# GZ7_1_x-SIM800C.net
KiCad netlist of a schematic drawn in Altium Designer
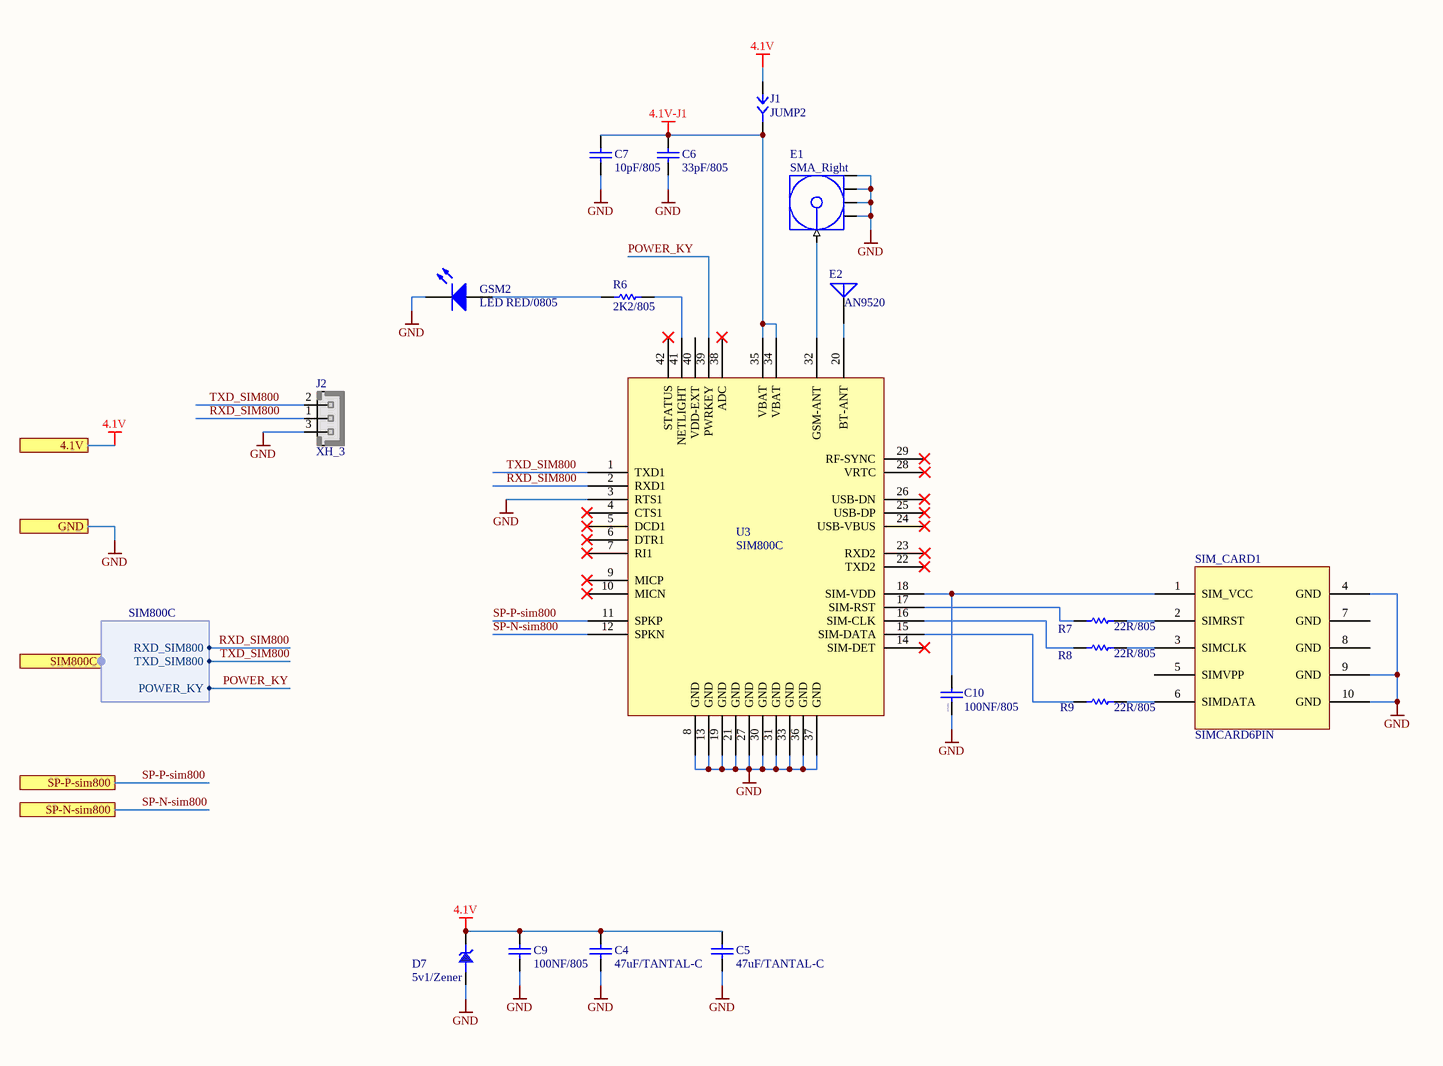
[diagram p0: GZ7_1_x-SIM800C.SchDoc]

(export (version "E")
  (design (tool "Eeschema 10.0.6"))
  (components
    (comp (ref "C4")
      (value "47uF/TANTAL-C")
      (footprint "C-TT1")
      (description "TANTAL")
      (libsource (lib "Miscellaneous Devices") (part "Cap Semi"))
    )
    (comp (ref "C5")
      (value "47uF/TANTAL-C")
      (footprint "C-TT1")
      (description "TANTAL")
      (libsource (lib "Miscellaneous Devices") (part "Cap Semi"))
    )
    (comp (ref "C6")
      (value "33pF/805")
      (footprint "MY805 COP")
      (description "CAP 0805")
      (fields (field (name "PUBLISHER") "Altium Limited"))
      (libsource (lib "Miscellaneous Devices") (part "Cap Semi"))
    )
    (comp (ref "C7")
      (value "10pF/805")
      (footprint "MY805 COP")
      (description "CAP 0805")
      (fields (field (name "PUBLISHER") "Altium Limited"))
      (libsource (lib "Miscellaneous Devices") (part "Cap Semi"))
    )
    (comp (ref "C9")
      (value "100NF/805")
      (footprint "MY805 COP")
      (description "CAP 0805")
      (fields (field (name "PUBLISHER") "Altium Limited"))
      (libsource (lib "Miscellaneous Devices") (part "Cap Semi"))
    )
    (comp (ref "C10")
      (value "100NF/805")
      (footprint "MY805 COP")
      (description "CAP 0805")
      (libsource (lib "GZ8_4_0") (part "CAP"))
    )
    (comp (ref "D7")
      (value "5v1/Zener")
      (footprint "my-DO5X.1.5")
      (libsource (lib "My Diods") (part "Zener"))
    )
    (comp (ref "E1")
      (value "SMA_Right")
      (footprint "MCX5.08-H5")
      (description "50 Ohm Impedance")
      (fields (field (name "PUBLISHER") "Altium Limited"))
      (libsource (lib "Miscellaneous Connectors") (part "COAX-F"))
    )
    (comp (ref "E2")
      (value "AN9520")
      (footprint "ANT-SMD")
      (description "Multilayer Chip Antenna")
      (fields (field (name "PUBLISHER") "Altium Limited"))
      (libsource (lib "Miscellaneous Devices") (part "Antenna"))
    )
    (comp (ref "GSM2")
      (value "LED RED/0805")
      (footprint "LED_SMD_0805")
      (fields (field (name "PUBLISHER") "Altium Limited"))
      (libsource (lib "Miscellaneous Devices") (part "LED2"))
    )
    (comp (ref "J1") (value "JUMP2") (footprint "JUMP3") (libsource (lib "Ebrahim") (part "JUMP2")))
    (comp (ref "J2")
      (value "XH_3")
      (footprint "XH_3")
      (description "PW10-x-M, JST-BxB-XH-A pitch: 2.5mm, 3A/250v")
      (fields (field (name "MANF") "JST") (field (name "MANF_P#") "B3B-XH-A"))
      (libsource (lib "altium-import") (part "root_0_XH_3_"))
    )
    (comp (ref "R6")
      (value "2K2/805")
      (footprint "my805")
      (description "RES 805")
      (libsource (lib "Miscellaneous Devices") (part "Res1"))
    )
    (comp (ref "R7")
      (value "22R/805")
      (footprint "my805")
      (description "RES 805")
      (fields (field (name "PUBLISHER") "Altium Limited"))
      (libsource (lib "Miscellaneous Devices") (part "Res1"))
    )
    (comp (ref "R8")
      (value "22R/805")
      (footprint "my805")
      (description "RES 805")
      (fields (field (name "PUBLISHER") "Altium Limited"))
      (libsource (lib "Miscellaneous Devices") (part "Res1"))
    )
    (comp (ref "R9")
      (value "22R/805")
      (footprint "my805")
      (description "RES 805")
      (fields (field (name "PUBLISHER") "Altium Limited"))
      (libsource (lib "Miscellaneous Devices") (part "Res1"))
    )
    (comp (ref "SIM_CARD1")
      (value "SIMCARD6PIN")
      (footprint "MinSim")
      (libsource (lib "MGZ8-V3") (part "SIMCARD6PIN"))
    )
    (comp (ref "U3") (value "SIM800C") (footprint "SIM800C_2") (libsource (lib "SIM") (part "SIM800C")))
  )
  (nets
    (net (code "2") (name "/POWER_KY") (class "Default")
      (node (ref "U3") (pin "39") (pinfunction "PWRKEY_39") (pintype "passive"))
    )
    (net (code "3") (name "/RXD_SIM800") (class "Default")
      (node (ref "J2") (pin "1") (pinfunction "1_1") (pintype "passive"))
      (node (ref "U3") (pin "2") (pinfunction "RXD1_2") (pintype "passive"))
    )
    (net (code "4") (name "/SP-N-sim800") (class "Default")
      (node (ref "U3") (pin "12") (pinfunction "SPKN_12") (pintype "passive"))
    )
    (net (code "5") (name "/SP-P-sim800") (class "Default")
      (node (ref "U3") (pin "11") (pinfunction "SPKP_11") (pintype "passive"))
    )
    (net (code "6") (name "/TXD_SIM800") (class "Default")
      (node (ref "J2") (pin "2") (pinfunction "2_2") (pintype "passive"))
      (node (ref "U3") (pin "1") (pinfunction "TXD1_1") (pintype "passive"))
    )
    (net (code "8") (name "4.1V") (class "Default")
      (node (ref "C4") (pin "1") (pinfunction "1_1") (pintype "passive"))
      (node (ref "C5") (pin "1") (pinfunction "1_1") (pintype "passive"))
      (node (ref "C9") (pin "1") (pinfunction "1_1") (pintype "passive"))
      (node (ref "D7") (pin "2") (pintype "passive"))
      (node (ref "J1") (pin "2") (pinfunction "2_2") (pintype "passive"))
    )
    (net (code "9") (name "4.1V-J1") (class "Default")
      (node (ref "C6") (pin "1") (pinfunction "1_1") (pintype "passive"))
      (node (ref "C7") (pin "1") (pinfunction "1_1") (pintype "passive"))
      (node (ref "J1") (pin "1") (pinfunction "1_1") (pintype "passive"))
      (node (ref "U3") (pin "34") (pinfunction "VBAT_34") (pintype "passive"))
      (node (ref "U3") (pin "35") (pinfunction "VBAT_35") (pintype "passive"))
    )
    (net (code "10") (name "GND") (class "Default")
      (node (ref "C10") (pin "1") (pinfunction "1_1") (pintype "passive"))
      (node (ref "C4") (pin "2") (pinfunction "2_2") (pintype "passive"))
      (node (ref "C5") (pin "2") (pinfunction "2_2") (pintype "passive"))
      (node (ref "C6") (pin "2") (pinfunction "2_2") (pintype "passive"))
      (node (ref "C7") (pin "2") (pinfunction "2_2") (pintype "passive"))
      (node (ref "C9") (pin "2") (pinfunction "2_2") (pintype "passive"))
      (node (ref "D7") (pin "1") (pintype "passive"))
      (node (ref "E1") (pin "2") (pinfunction "GND_2") (pintype "power_in"))
      (node (ref "E1") (pin "3") (pinfunction "GND_3") (pintype "power_in"))
      (node (ref "E1") (pin "4") (pinfunction "GND_4") (pintype "power_in"))
      (node (ref "E1") (pin "5") (pinfunction "GND_5") (pintype "power_in"))
      (node (ref "GSM2") (pin "2") (pinfunction "K_2") (pintype "passive"))
      (node (ref "J2") (pin "3") (pinfunction "3_3") (pintype "passive"))
      (node (ref "SIM_CARD1") (pin "10") (pinfunction "GND_10") (pintype "passive"))
      (node (ref "SIM_CARD1") (pin "4") (pinfunction "GND_4") (pintype "passive"))
      (node (ref "SIM_CARD1") (pin "9") (pinfunction "GND_9") (pintype "passive"))
      (node (ref "U3") (pin "13") (pinfunction "GND_13") (pintype "passive"))
      (node (ref "U3") (pin "19") (pinfunction "GND_19") (pintype "passive"))
      (node (ref "U3") (pin "21") (pinfunction "GND_21") (pintype "passive"))
      (node (ref "U3") (pin "27") (pinfunction "GND_27") (pintype "passive"))
      (node (ref "U3") (pin "3") (pinfunction "RTS1_3") (pintype "passive"))
      (node (ref "U3") (pin "30") (pinfunction "GND_30") (pintype "passive"))
      (node (ref "U3") (pin "31") (pinfunction "GND_31") (pintype "passive"))
      (node (ref "U3") (pin "33") (pinfunction "GND_33") (pintype "passive"))
      (node (ref "U3") (pin "36") (pinfunction "GND_36") (pintype "passive"))
      (node (ref "U3") (pin "37") (pinfunction "GND_37") (pintype "passive"))
      (node (ref "U3") (pin "8") (pinfunction "GND_8") (pintype "passive"))
    )
    (net (code "11") (name "Net-(E1-Signal)") (class "Default")
      (node (ref "E1") (pin "1") (pinfunction "Signal_1") (pintype "input"))
      (node (ref "U3") (pin "32") (pinfunction "GSM-ANT_32") (pintype "passive"))
    )
    (net (code "12") (name "Net-(E2-A)") (class "Default")
      (node (ref "E2") (pin "1") (pinfunction "A_1") (pintype "passive"))
      (node (ref "U3") (pin "20") (pinfunction "BT-ANT_20") (pintype "passive"))
    )
    (net (code "13") (name "Net-(GSM2-A)") (class "Default")
      (node (ref "GSM2") (pin "1") (pinfunction "A_1") (pintype "passive"))
      (node (ref "R6") (pin "1") (pinfunction "1_1") (pintype "passive"))
    )
    (net (code "14") (name "Net-(SIM_CARD1-SIMCLK)") (class "Default")
      (node (ref "R8") (pin "1") (pinfunction "1_1") (pintype "passive"))
      (node (ref "SIM_CARD1") (pin "3") (pinfunction "SIMCLK_3") (pintype "passive"))
    )
    (net (code "15") (name "Net-(SIM_CARD1-SIMDATA)") (class "Default")
      (node (ref "R9") (pin "1") (pinfunction "1_1") (pintype "passive"))
      (node (ref "SIM_CARD1") (pin "6") (pinfunction "SIMDATA_6") (pintype "passive"))
    )
    (net (code "16") (name "Net-(SIM_CARD1-SIMRST)") (class "Default")
      (node (ref "R7") (pin "1") (pinfunction "1_1") (pintype "passive"))
      (node (ref "SIM_CARD1") (pin "2") (pinfunction "SIMRST_2") (pintype "passive"))
    )
    (net (code "17") (name "Net-(SIM_CARD1-SIM_VCC)") (class "Default")
      (node (ref "C10") (pin "2") (pinfunction "2_2") (pintype "passive"))
      (node (ref "SIM_CARD1") (pin "1") (pinfunction "SIM_VCC_1") (pintype "passive"))
      (node (ref "U3") (pin "18") (pinfunction "SIM-VDD_18") (pintype "passive"))
    )
    (net (code "18") (name "Net-(U3-NETLIGHT)") (class "Default")
      (node (ref "R6") (pin "2") (pinfunction "2_2") (pintype "passive"))
      (node (ref "U3") (pin "41") (pinfunction "NETLIGHT_41") (pintype "passive"))
    )
    (net (code "19") (name "Net-(U3-SIM-CLK)") (class "Default")
      (node (ref "R8") (pin "2") (pinfunction "2_2") (pintype "passive"))
      (node (ref "U3") (pin "16") (pinfunction "SIM-CLK_16") (pintype "passive"))
    )
    (net (code "20") (name "Net-(U3-SIM-DATA)") (class "Default")
      (node (ref "R9") (pin "2") (pinfunction "2_2") (pintype "passive"))
      (node (ref "U3") (pin "15") (pinfunction "SIM-DATA_15") (pintype "passive"))
    )
    (net (code "21") (name "Net-(U3-SIM-RST)") (class "Default")
      (node (ref "R7") (pin "2") (pinfunction "2_2") (pintype "passive"))
      (node (ref "U3") (pin "17") (pinfunction "SIM-RST_17") (pintype "passive"))
    )
    (net (code "22") (name "unconnected-(SIM_CARD1-GND-Pad7)") (class "Default")
      (node (ref "SIM_CARD1") (pin "7") (pinfunction "GND_7") (pintype "passive"))
    )
    (net (code "23") (name "unconnected-(SIM_CARD1-GND-Pad8)") (class "Default")
      (node (ref "SIM_CARD1") (pin "8") (pinfunction "GND_8") (pintype "passive"))
    )
    (net (code "24") (name "unconnected-(SIM_CARD1-SIMVPP-Pad5)") (class "Default")
      (node (ref "SIM_CARD1") (pin "5") (pinfunction "SIMVPP_5") (pintype "passive"))
    )
    (net (code "25") (name "unconnected-(U3-ADC-Pad38)") (class "Default")
      (node (ref "U3") (pin "38") (pinfunction "ADC_38") (pintype "passive+no_connect"))
    )
    (net (code "26") (name "unconnected-(U3-CTS1-Pad4)") (class "Default")
      (node (ref "U3") (pin "4") (pinfunction "CTS1_4") (pintype "passive+no_connect"))
    )
    (net (code "27") (name "unconnected-(U3-DCD1-Pad5)") (class "Default")
      (node (ref "U3") (pin "5") (pinfunction "DCD1_5") (pintype "passive+no_connect"))
    )
    (net (code "28") (name "unconnected-(U3-DTR1-Pad6)") (class "Default")
      (node (ref "U3") (pin "6") (pinfunction "DTR1_6") (pintype "passive+no_connect"))
    )
    (net (code "29") (name "unconnected-(U3-MICN-Pad10)") (class "Default")
      (node (ref "U3") (pin "10") (pinfunction "MICN_10") (pintype "passive+no_connect"))
    )
    (net (code "30") (name "unconnected-(U3-MICP-Pad9)") (class "Default")
      (node (ref "U3") (pin "9") (pinfunction "MICP_9") (pintype "passive+no_connect"))
    )
    (net (code "31") (name "unconnected-(U3-RF-SYNC-Pad29)") (class "Default")
      (node (ref "U3") (pin "29") (pinfunction "RF-SYNC_29") (pintype "passive+no_connect"))
    )
    (net (code "32") (name "unconnected-(U3-RI1-Pad7)") (class "Default")
      (node (ref "U3") (pin "7") (pinfunction "RI1_7") (pintype "passive+no_connect"))
    )
    (net (code "33") (name "unconnected-(U3-RXD2-Pad23)") (class "Default")
      (node (ref "U3") (pin "23") (pinfunction "RXD2_23") (pintype "passive"))
    )
    (net (code "34") (name "unconnected-(U3-SIM-DET-Pad14)") (class "Default")
      (node (ref "U3") (pin "14") (pinfunction "SIM-DET_14") (pintype "passive+no_connect"))
    )
    (net (code "35") (name "unconnected-(U3-STATUS-Pad42)") (class "Default")
      (node (ref "U3") (pin "42") (pinfunction "STATUS_42") (pintype "passive"))
    )
    (net (code "36") (name "unconnected-(U3-TXD2-Pad22)") (class "Default")
      (node (ref "U3") (pin "22") (pinfunction "TXD2_22") (pintype "passive+no_connect"))
    )
    (net (code "37") (name "unconnected-(U3-USB-DN-Pad26)") (class "Default")
      (node (ref "U3") (pin "26") (pinfunction "USB-DN_26") (pintype "passive+no_connect"))
    )
    (net (code "38") (name "unconnected-(U3-USB-DP-Pad25)") (class "Default")
      (node (ref "U3") (pin "25") (pinfunction "USB-DP_25") (pintype "passive+no_connect"))
    )
    (net (code "39") (name "unconnected-(U3-USB-VBUS-Pad24)") (class "Default")
      (node (ref "U3") (pin "24") (pinfunction "USB-VBUS_24") (pintype "passive+no_connect"))
    )
    (net (code "40") (name "unconnected-(U3-VDD-EXT-Pad40)") (class "Default")
      (node (ref "U3") (pin "40") (pinfunction "VDD-EXT_40") (pintype "passive"))
    )
    (net (code "41") (name "unconnected-(U3-VRTC-Pad28)") (class "Default")
      (node (ref "U3") (pin "28") (pinfunction "VRTC_28") (pintype "passive"))
    )
  )
)
